# mkr100.net
KiCad netlist of a schematic drawn in EAGLE
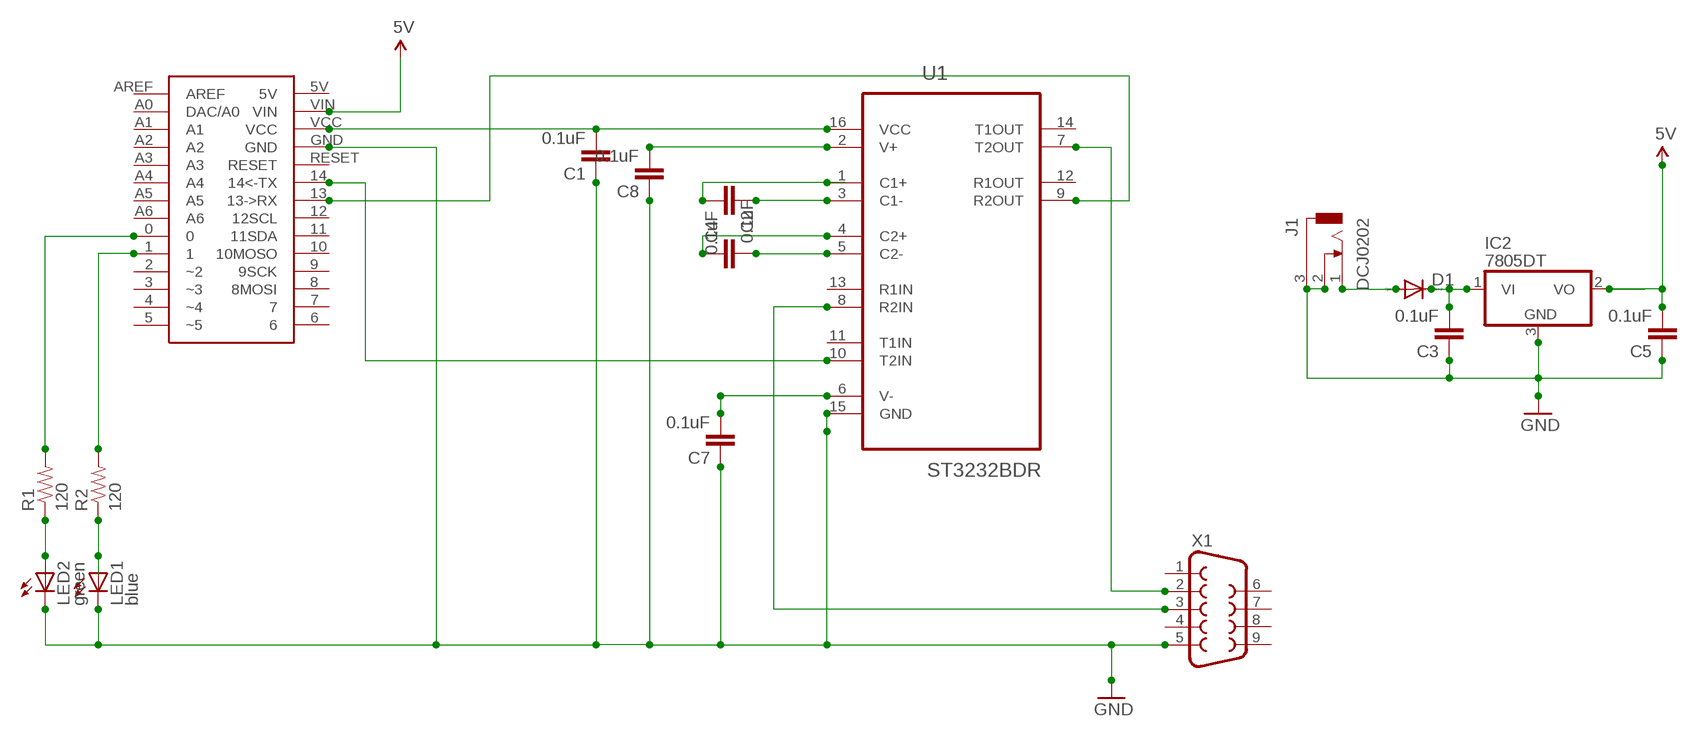
[diagram p0: schematic, sheet 1]

(export (version "E")
  (design (tool "Eeschema 10.0.6"))
  (components
    (comp (ref "C1")
      (value "0.1uF")
      (footprint "eagle-import:0603-CAP")
      (libsource (lib "eagle-import") (part "0.1UF-25V(+80/-20%)(0603)"))
    )
    (comp (ref "C2")
      (value "0.1uF")
      (footprint "eagle-import:0603-CAP")
      (libsource (lib "eagle-import") (part "0.1UF-25V(+80/-20%)(0603)"))
    )
    (comp (ref "C3")
      (value "0.1uF")
      (footprint "eagle-import:0603-CAP")
      (libsource (lib "eagle-import") (part "0.1UF-25V(+80/-20%)(0603)"))
    )
    (comp (ref "C4")
      (value "0.1uF")
      (footprint "eagle-import:0603-CAP")
      (libsource (lib "eagle-import") (part "0.1UF-25V(+80/-20%)(0603)"))
    )
    (comp (ref "C5")
      (value "0.1uF")
      (footprint "eagle-import:0603-CAP")
      (libsource (lib "eagle-import") (part "0.1UF-25V(+80/-20%)(0603)"))
    )
    (comp (ref "C7")
      (value "0.1uF")
      (footprint "eagle-import:0603-CAP")
      (libsource (lib "eagle-import") (part "0.1UF-25V(+80/-20%)(0603)"))
    )
    (comp (ref "C8")
      (value "0.1uF")
      (footprint "eagle-import:0603-CAP")
      (libsource (lib "eagle-import") (part "0.1UF-25V(+80/-20%)(0603)"))
    )
    (comp (ref "D1")
      (value "DIODE-SMB")
      (footprint "eagle-import:SMB")
      (libsource (lib "eagle-import") (part "DIODE-SMB"))
    )
    (comp (ref "IC2")
      (value "7805DT")
      (footprint "eagle-import:TO252")
      (libsource (lib "eagle-import") (part "78DT05"))
    )
    (comp (ref "J1")
      (value "DCJ0202")
      (footprint "eagle-import:DCJ0202")
      (libsource (lib "eagle-import") (part "DCJ0202"))
    )
    (comp (ref "LED1")
      (value "blue")
      (footprint "eagle-import:SML0805")
      (libsource (lib "eagle-import") (part "LEDSML0805"))
    )
    (comp (ref "LED2")
      (value "green")
      (footprint "eagle-import:SML0805")
      (libsource (lib "eagle-import") (part "LEDSML0805"))
    )
    (comp (ref "R1")
      (value "120")
      (footprint "eagle-import:0805")
      (libsource (lib "eagle-import") (part "RESISTOR0805-RES"))
    )
    (comp (ref "R2")
      (value "120")
      (footprint "eagle-import:0805")
      (libsource (lib "eagle-import") (part "RESISTOR0805-RES"))
    )
    (comp (ref "U$1")
      (value "MKR1000")
      (footprint "eagle-import:MKR1000")
      (libsource (lib "eagle-import") (part "MKR1000"))
    )
    (comp (ref "U1")
      (value "ST3232BDR")
      (footprint "eagle-import:SOIC127P600X175-16N")
      (libsource (lib "eagle-import") (part "ST3232BDR"))
    )
    (comp (ref "X1")
      (value "DB9FEMALE")
      (footprint "eagle-import:DB9")
      (libsource (lib "eagle-import") (part "DB9FEMALE"))
    )
  )
  (nets
    (net (code "1") (name "5V") (class "Default")
      (node (ref "C5") (pin "2") (pinfunction "2_2") (pintype "passive"))
      (node (ref "IC2") (pin "2") (pinfunction "VO_2") (pintype "passive"))
      (node (ref "U$1") (pin "VIN") (pinfunction "VIN_VIN") (pintype "bidirectional"))
    )
    (net (code "2") (name "GND") (class "Default")
      (node (ref "C1") (pin "1") (pinfunction "1_1") (pintype "passive"))
      (node (ref "C3") (pin "1") (pinfunction "1_1") (pintype "passive"))
      (node (ref "C5") (pin "1") (pinfunction "1_1") (pintype "passive"))
      (node (ref "C7") (pin "1") (pinfunction "1_1") (pintype "passive"))
      (node (ref "C8") (pin "1") (pinfunction "1_1") (pintype "passive"))
      (node (ref "IC2") (pin "3") (pinfunction "GND_3") (pintype "passive"))
      (node (ref "J1") (pin "2") (pinfunction "2_2") (pintype "passive"))
      (node (ref "J1") (pin "3") (pinfunction "1_3") (pintype "passive"))
      (node (ref "LED1") (pin "C") (pinfunction "C_C") (pintype "passive"))
      (node (ref "LED2") (pin "C") (pinfunction "C_C") (pintype "passive"))
      (node (ref "U$1") (pin "GND") (pinfunction "GND_GND") (pintype "bidirectional"))
      (node (ref "U1") (pin "15") (pinfunction "GND_15") (pintype "passive"))
      (node (ref "X1") (pin "5") (pinfunction "5_5") (pintype "passive"))
    )
    (net (code "3") (name "Net-(IC2-VI)") (class "Default")
      (node (ref "C3") (pin "2") (pinfunction "2_2") (pintype "passive"))
      (node (ref "D1") (pin "C") (pinfunction "C_C") (pintype "passive"))
      (node (ref "IC2") (pin "1") (pinfunction "VI_1") (pintype "input"))
    )
    (net (code "4") (name "Net-(J1-3)") (class "Default")
      (node (ref "D1") (pin "A") (pinfunction "A_A") (pintype "passive"))
      (node (ref "J1") (pin "1") (pinfunction "3_1") (pintype "passive"))
    )
    (net (code "5") (name "Net-(LED1-PadA)") (class "Default")
      (node (ref "LED1") (pin "A") (pinfunction "A_A") (pintype "passive"))
      (node (ref "R2") (pin "1") (pinfunction "1_1") (pintype "passive"))
    )
    (net (code "6") (name "Net-(LED2-PadA)") (class "Default")
      (node (ref "LED2") (pin "A") (pinfunction "A_A") (pintype "passive"))
      (node (ref "R1") (pin "1") (pinfunction "1_1") (pintype "passive"))
    )
    (net (code "7") (name "Net-(R1-Pad2)") (class "Default")
      (node (ref "R1") (pin "2") (pinfunction "2_2") (pintype "passive"))
      (node (ref "U$1") (pin "0") (pinfunction "0_0") (pintype "bidirectional"))
    )
    (net (code "8") (name "Net-(R2-Pad2)") (class "Default")
      (node (ref "R2") (pin "2") (pinfunction "2_2") (pintype "passive"))
      (node (ref "U$1") (pin "1") (pinfunction "1_1") (pintype "bidirectional"))
    )
    (net (code "9") (name "Net-(U$1-13->RX)") (class "Default")
      (node (ref "U$1") (pin "13") (pinfunction "13->RX_13") (pintype "bidirectional"))
      (node (ref "U1") (pin "9") (pinfunction "R2OUT_9") (pintype "output"))
    )
    (net (code "10") (name "Net-(U$1-14<-TX)") (class "Default")
      (node (ref "U$1") (pin "14") (pinfunction "14<-TX_14") (pintype "bidirectional"))
      (node (ref "U1") (pin "10") (pinfunction "T2IN_10") (pintype "input"))
    )
    (net (code "11") (name "Net-(U1-C1+)") (class "Default")
      (node (ref "C2") (pin "2") (pinfunction "2_2") (pintype "passive"))
      (node (ref "U1") (pin "1") (pinfunction "C1+_1") (pintype "passive"))
    )
    (net (code "12") (name "Net-(U1-C1-)") (class "Default")
      (node (ref "C2") (pin "1") (pinfunction "1_1") (pintype "passive"))
      (node (ref "U1") (pin "3") (pinfunction "C1-_3") (pintype "passive"))
    )
    (net (code "13") (name "Net-(U1-C2+)") (class "Default")
      (node (ref "C4") (pin "1") (pinfunction "1_1") (pintype "passive"))
      (node (ref "U1") (pin "4") (pinfunction "C2+_4") (pintype "passive"))
    )
    (net (code "14") (name "Net-(U1-C2-)") (class "Default")
      (node (ref "C4") (pin "2") (pinfunction "2_2") (pintype "passive"))
      (node (ref "U1") (pin "5") (pinfunction "C2-_5") (pintype "passive"))
    )
    (net (code "15") (name "Net-(U1-R2IN)") (class "Default")
      (node (ref "U1") (pin "8") (pinfunction "R2IN_8") (pintype "input"))
      (node (ref "X1") (pin "3") (pinfunction "3_3") (pintype "passive"))
    )
    (net (code "16") (name "Net-(U1-T2OUT)") (class "Default")
      (node (ref "U1") (pin "7") (pinfunction "T2OUT_7") (pintype "output"))
      (node (ref "X1") (pin "2") (pinfunction "2_2") (pintype "passive"))
    )
    (net (code "17") (name "Net-(U1-V+)") (class "Default")
      (node (ref "C8") (pin "2") (pinfunction "2_2") (pintype "passive"))
      (node (ref "U1") (pin "2") (pinfunction "V+_2") (pintype "power_in"))
    )
    (net (code "18") (name "Net-(U1-V-)") (class "Default")
      (node (ref "C7") (pin "2") (pinfunction "2_2") (pintype "passive"))
      (node (ref "U1") (pin "6") (pinfunction "V-_6") (pintype "power_in"))
    )
    (net (code "19") (name "Net-(U1-VCC)") (class "Default")
      (node (ref "C1") (pin "2") (pinfunction "2_2") (pintype "passive"))
      (node (ref "U$1") (pin "VCC") (pinfunction "VCC_VCC") (pintype "bidirectional"))
      (node (ref "U1") (pin "16") (pinfunction "VCC_16") (pintype "power_in"))
    )
    (net (code "20") (name "unconnected-(U$1-8MOSI-Pad8)") (class "Default")
      (node (ref "U$1") (pin "8") (pinfunction "8MOSI_8") (pintype "bidirectional"))
    )
    (net (code "21") (name "unconnected-(U$1-9SCK-Pad9)") (class "Default")
      (node (ref "U$1") (pin "9") (pinfunction "9SCK_9") (pintype "bidirectional"))
    )
    (net (code "22") (name "unconnected-(U$1-10MOSO-Pad10)") (class "Default")
      (node (ref "U$1") (pin "10") (pinfunction "10MOSO_10") (pintype "bidirectional"))
    )
    (net (code "23") (name "unconnected-(U$1-11SDA-Pad11)") (class "Default")
      (node (ref "U$1") (pin "11") (pinfunction "11SDA_11") (pintype "bidirectional"))
    )
    (net (code "24") (name "unconnected-(U$1-12SCL-Pad12)") (class "Default")
      (node (ref "U$1") (pin "12") (pinfunction "12SCL_12") (pintype "bidirectional"))
    )
    (net (code "25") (name "unconnected-(U$1-DAC{slash}A0-PadA0)") (class "Default")
      (node (ref "U$1") (pin "A0") (pinfunction "DAC/A0_A0") (pintype "bidirectional"))
    )
    (net (code "26") (name "unconnected-(U$1-Pad5V)") (class "Default")
      (node (ref "U$1") (pin "5V") (pinfunction "5V_5V") (pintype "bidirectional"))
    )
    (net (code "27") (name "unconnected-(U$1-Pad6)") (class "Default")
      (node (ref "U$1") (pin "6") (pinfunction "6_6") (pintype "bidirectional"))
    )
    (net (code "28") (name "unconnected-(U$1-Pad7)") (class "Default")
      (node (ref "U$1") (pin "7") (pinfunction "7_7") (pintype "bidirectional"))
    )
    (net (code "29") (name "unconnected-(U$1-PadA1)") (class "Default")
      (node (ref "U$1") (pin "A1") (pinfunction "A1_A1") (pintype "bidirectional"))
    )
    (net (code "30") (name "unconnected-(U$1-PadA2)") (class "Default")
      (node (ref "U$1") (pin "A2") (pinfunction "A2_A2") (pintype "bidirectional"))
    )
    (net (code "31") (name "unconnected-(U$1-PadA3)") (class "Default")
      (node (ref "U$1") (pin "A3") (pinfunction "A3_A3") (pintype "bidirectional"))
    )
    (net (code "32") (name "unconnected-(U$1-PadA4)") (class "Default")
      (node (ref "U$1") (pin "A4") (pinfunction "A4_A4") (pintype "bidirectional"))
    )
    (net (code "33") (name "unconnected-(U$1-PadA5)") (class "Default")
      (node (ref "U$1") (pin "A5") (pinfunction "A5_A5") (pintype "bidirectional"))
    )
    (net (code "34") (name "unconnected-(U$1-PadA6)") (class "Default")
      (node (ref "U$1") (pin "A6") (pinfunction "A6_A6") (pintype "bidirectional"))
    )
    (net (code "35") (name "unconnected-(U$1-PadAREF)") (class "Default")
      (node (ref "U$1") (pin "AREF") (pinfunction "AREF_AREF") (pintype "bidirectional"))
    )
    (net (code "36") (name "unconnected-(U$1-PadRESET)") (class "Default")
      (node (ref "U$1") (pin "RESET") (pinfunction "RESET_RESET") (pintype "bidirectional"))
    )
    (net (code "37") (name "unconnected-(U$1-~{2}-Pad2)") (class "Default")
      (node (ref "U$1") (pin "2") (pinfunction "~{2}_2") (pintype "bidirectional"))
    )
    (net (code "38") (name "unconnected-(U$1-~{3}-Pad3)") (class "Default")
      (node (ref "U$1") (pin "3") (pinfunction "~{3}_3") (pintype "bidirectional"))
    )
    (net (code "39") (name "unconnected-(U$1-~{4}-Pad4)") (class "Default")
      (node (ref "U$1") (pin "4") (pinfunction "~{4}_4") (pintype "bidirectional"))
    )
    (net (code "40") (name "unconnected-(U$1-~{5}-Pad5)") (class "Default")
      (node (ref "U$1") (pin "5") (pinfunction "~{5}_5") (pintype "bidirectional"))
    )
    (net (code "41") (name "unconnected-(U1-R1IN-Pad13)") (class "Default")
      (node (ref "U1") (pin "13") (pinfunction "R1IN_13") (pintype "input"))
    )
    (net (code "42") (name "unconnected-(U1-R1OUT-Pad12)") (class "Default")
      (node (ref "U1") (pin "12") (pinfunction "R1OUT_12") (pintype "output"))
    )
    (net (code "43") (name "unconnected-(U1-T1IN-Pad11)") (class "Default")
      (node (ref "U1") (pin "11") (pinfunction "T1IN_11") (pintype "input"))
    )
    (net (code "44") (name "unconnected-(U1-T1OUT-Pad14)") (class "Default")
      (node (ref "U1") (pin "14") (pinfunction "T1OUT_14") (pintype "output"))
    )
    (net (code "45") (name "unconnected-(X1-Pad1)") (class "Default")
      (node (ref "X1") (pin "1") (pinfunction "1_1") (pintype "passive"))
    )
    (net (code "46") (name "unconnected-(X1-Pad4)") (class "Default")
      (node (ref "X1") (pin "4") (pinfunction "4_4") (pintype "passive"))
    )
    (net (code "47") (name "unconnected-(X1-Pad6)") (class "Default")
      (node (ref "X1") (pin "6") (pinfunction "6_6") (pintype "passive"))
    )
    (net (code "48") (name "unconnected-(X1-Pad7)") (class "Default")
      (node (ref "X1") (pin "7") (pinfunction "7_7") (pintype "passive"))
    )
    (net (code "49") (name "unconnected-(X1-Pad8)") (class "Default")
      (node (ref "X1") (pin "8") (pinfunction "8_8") (pintype "passive"))
    )
    (net (code "50") (name "unconnected-(X1-Pad9)") (class "Default")
      (node (ref "X1") (pin "9") (pinfunction "9_9") (pintype "passive"))
    )
  )
)
